# ojacevalec.net
KiCad netlist of a schematic drawn in EAGLE
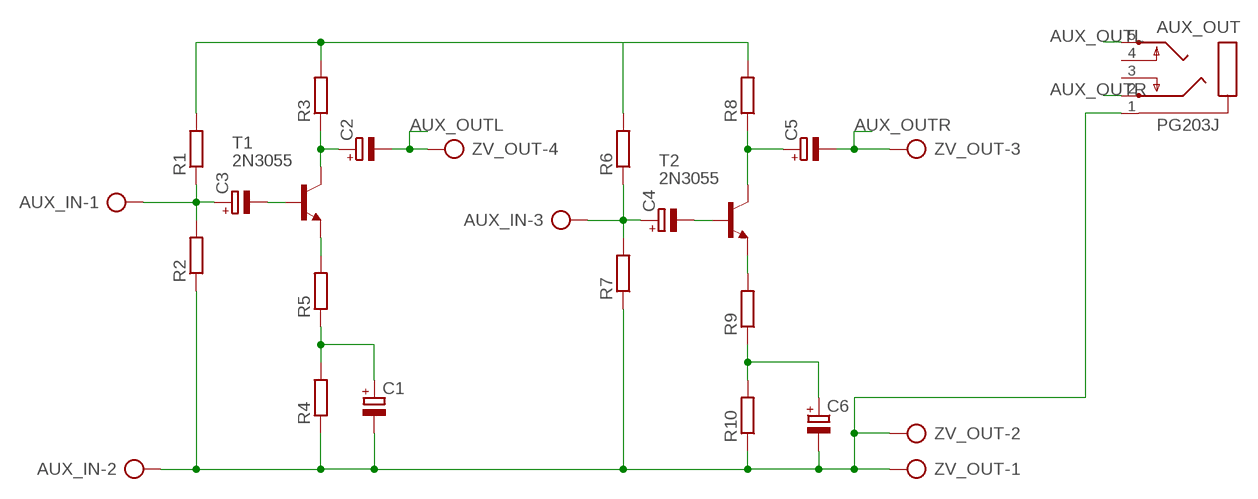
[diagram p0: schematic, sheet 1]

(export (version "E")
  (design (tool "Eeschema 10.0.6"))
  (components
    (comp (ref "AUX_IN")
      (value "AK300/3")
      (footprint "eagle-import:AK300_3")
      (libsource (lib "eagle-import") (part "AK300/3"))
    )
    (comp (ref "AUX_OUT")
      (value "PG203J")
      (footprint "eagle-import:PG203J")
      (libsource (lib "eagle-import") (part "PG203J"))
    )
    (comp (ref "C1")
      (value "CPOL-EUTT5D10")
      (footprint "eagle-import:TT5D10")
      (libsource (lib "eagle-import") (part "CPOL-EUTT5D10"))
    )
    (comp (ref "C2")
      (value "CPOL-EUTT5D10")
      (footprint "eagle-import:TT5D10")
      (libsource (lib "eagle-import") (part "CPOL-EUTT5D10"))
    )
    (comp (ref "C3")
      (value "CPOL-EUTT5D10")
      (footprint "eagle-import:TT5D10")
      (libsource (lib "eagle-import") (part "CPOL-EUTT5D10"))
    )
    (comp (ref "C4")
      (value "CPOL-EUTT5D10")
      (footprint "eagle-import:TT5D10")
      (libsource (lib "eagle-import") (part "CPOL-EUTT5D10"))
    )
    (comp (ref "C5")
      (value "CPOL-EUTT5D10")
      (footprint "eagle-import:TT5D10")
      (libsource (lib "eagle-import") (part "CPOL-EUTT5D10"))
    )
    (comp (ref "C6")
      (value "CPOL-EUTT5D10")
      (footprint "eagle-import:TT5D10")
      (libsource (lib "eagle-import") (part "CPOL-EUTT5D10"))
    )
    (comp (ref "R1")
      (value "R-EU_0309/12")
      (footprint "eagle-import:0309_12")
      (libsource (lib "eagle-import") (part "R-EU_0309/12"))
    )
    (comp (ref "R2")
      (value "R-EU_0309/12")
      (footprint "eagle-import:0309_12")
      (libsource (lib "eagle-import") (part "R-EU_0309/12"))
    )
    (comp (ref "R3")
      (value "R-EU_0309/12")
      (footprint "eagle-import:0309_12")
      (libsource (lib "eagle-import") (part "R-EU_0309/12"))
    )
    (comp (ref "R4")
      (value "R-EU_0309/12")
      (footprint "eagle-import:0309_12")
      (libsource (lib "eagle-import") (part "R-EU_0309/12"))
    )
    (comp (ref "R5")
      (value "R-EU_0309/12")
      (footprint "eagle-import:0309_12")
      (libsource (lib "eagle-import") (part "R-EU_0309/12"))
    )
    (comp (ref "R6")
      (value "R-EU_0309/12")
      (footprint "eagle-import:0309_12")
      (libsource (lib "eagle-import") (part "R-EU_0309/12"))
    )
    (comp (ref "R7")
      (value "R-EU_0309/12")
      (footprint "eagle-import:0309_12")
      (libsource (lib "eagle-import") (part "R-EU_0309/12"))
    )
    (comp (ref "R8")
      (value "R-EU_0309/12")
      (footprint "eagle-import:0309_12")
      (libsource (lib "eagle-import") (part "R-EU_0309/12"))
    )
    (comp (ref "R9")
      (value "R-EU_0309/12")
      (footprint "eagle-import:0309_12")
      (libsource (lib "eagle-import") (part "R-EU_0309/12"))
    )
    (comp (ref "R10")
      (value "R-EU_0309/12")
      (footprint "eagle-import:0309_12")
      (libsource (lib "eagle-import") (part "R-EU_0309/12"))
    )
    (comp (ref "T1")
      (value "2N3055")
      (footprint "eagle-import:TO3")
      (libsource (lib "eagle-import") (part "2N3055"))
    )
    (comp (ref "T2")
      (value "2N3055")
      (footprint "eagle-import:TO3")
      (libsource (lib "eagle-import") (part "2N3055"))
    )
    (comp (ref "ZV_OUT")
      (value "AK300/4")
      (footprint "eagle-import:AK300_4")
      (libsource (lib "eagle-import") (part "AK300/4"))
    )
  )
  (nets
    (net (code "1") (name "/AUX_OUTL") (class "Default")
      (node (ref "AUX_OUT") (pin "5") (pinfunction "5_5") (pintype "passive"))
      (node (ref "C2") (pin "-") (pinfunction "-_-") (pintype "passive"))
      (node (ref "ZV_OUT") (pin "4") (pinfunction "KL_4") (pintype "passive"))
    )
    (net (code "2") (name "/AUX_OUTR") (class "Default")
      (node (ref "AUX_OUT") (pin "2") (pinfunction "2_2") (pintype "passive"))
      (node (ref "C5") (pin "-") (pinfunction "-_-") (pintype "passive"))
      (node (ref "ZV_OUT") (pin "3") (pinfunction "KL_3") (pintype "passive"))
    )
    (net (code "3") (name "Net-(AUX_INA-KL)") (class "Default")
      (node (ref "AUX_IN") (pin "1") (pinfunction "KL_1") (pintype "passive"))
      (node (ref "C3") (pin "+") (pinfunction "+_+") (pintype "passive"))
      (node (ref "R1") (pin "1") (pinfunction "1_1") (pintype "passive"))
      (node (ref "R2") (pin "2") (pinfunction "2_2") (pintype "passive"))
    )
    (net (code "4") (name "Net-(AUX_INB-KL)") (class "Default")
      (node (ref "AUX_IN") (pin "2") (pinfunction "KL_2") (pintype "passive"))
      (node (ref "AUX_OUT") (pin "1") (pinfunction "1_1") (pintype "passive"))
      (node (ref "C1") (pin "-") (pinfunction "-_-") (pintype "passive"))
      (node (ref "C6") (pin "-") (pinfunction "-_-") (pintype "passive"))
      (node (ref "R10") (pin "1") (pinfunction "1_1") (pintype "passive"))
      (node (ref "R2") (pin "1") (pinfunction "1_1") (pintype "passive"))
      (node (ref "R4") (pin "1") (pinfunction "1_1") (pintype "passive"))
      (node (ref "R7") (pin "1") (pinfunction "1_1") (pintype "passive"))
      (node (ref "ZV_OUT") (pin "1") (pinfunction "KL_1") (pintype "passive"))
      (node (ref "ZV_OUT") (pin "2") (pinfunction "KL_2") (pintype "passive"))
    )
    (net (code "5") (name "Net-(AUX_INC-KL)") (class "Default")
      (node (ref "AUX_IN") (pin "3") (pinfunction "KL_3") (pintype "passive"))
      (node (ref "C4") (pin "+") (pinfunction "+_+") (pintype "passive"))
      (node (ref "R6") (pin "1") (pinfunction "1_1") (pintype "passive"))
      (node (ref "R7") (pin "2") (pinfunction "2_2") (pintype "passive"))
    )
    (net (code "6") (name "Net-(C1-Pad+)") (class "Default")
      (node (ref "C1") (pin "+") (pinfunction "+_+") (pintype "passive"))
      (node (ref "R4") (pin "2") (pinfunction "2_2") (pintype "passive"))
      (node (ref "R5") (pin "1") (pinfunction "1_1") (pintype "passive"))
    )
    (net (code "7") (name "Net-(C2-Pad+)") (class "Default")
      (node (ref "C2") (pin "+") (pinfunction "+_+") (pintype "passive"))
      (node (ref "R3") (pin "1") (pinfunction "1_1") (pintype "passive"))
      (node (ref "T1") (pin "C") (pinfunction "C_C") (pintype "passive"))
      (node (ref "T1") (pin "C/") (pinfunction "C_C/") (pintype "passive"))
    )
    (net (code "8") (name "Net-(C3-Pad-)") (class "Default")
      (node (ref "C3") (pin "-") (pinfunction "-_-") (pintype "passive"))
      (node (ref "T1") (pin "B") (pinfunction "B_B") (pintype "passive"))
    )
    (net (code "9") (name "Net-(C4-Pad-)") (class "Default")
      (node (ref "C4") (pin "-") (pinfunction "-_-") (pintype "passive"))
      (node (ref "T2") (pin "B") (pinfunction "B_B") (pintype "passive"))
    )
    (net (code "10") (name "Net-(C5-Pad+)") (class "Default")
      (node (ref "C5") (pin "+") (pinfunction "+_+") (pintype "passive"))
      (node (ref "R8") (pin "1") (pinfunction "1_1") (pintype "passive"))
      (node (ref "T2") (pin "C") (pinfunction "C_C") (pintype "passive"))
      (node (ref "T2") (pin "C/") (pinfunction "C_C/") (pintype "passive"))
    )
    (net (code "11") (name "Net-(C6-Pad+)") (class "Default")
      (node (ref "C6") (pin "+") (pinfunction "+_+") (pintype "passive"))
      (node (ref "R10") (pin "2") (pinfunction "2_2") (pintype "passive"))
      (node (ref "R9") (pin "1") (pinfunction "1_1") (pintype "passive"))
    )
    (net (code "12") (name "Net-(R1-Pad2)") (class "Default")
      (node (ref "R1") (pin "2") (pinfunction "2_2") (pintype "passive"))
      (node (ref "R3") (pin "2") (pinfunction "2_2") (pintype "passive"))
      (node (ref "R6") (pin "2") (pinfunction "2_2") (pintype "passive"))
      (node (ref "R8") (pin "2") (pinfunction "2_2") (pintype "passive"))
    )
    (net (code "13") (name "Net-(R5-Pad2)") (class "Default")
      (node (ref "R5") (pin "2") (pinfunction "2_2") (pintype "passive"))
      (node (ref "T1") (pin "E") (pinfunction "E_E") (pintype "passive"))
    )
    (net (code "14") (name "Net-(R9-Pad2)") (class "Default")
      (node (ref "R9") (pin "2") (pinfunction "2_2") (pintype "passive"))
      (node (ref "T2") (pin "E") (pinfunction "E_E") (pintype "passive"))
    )
    (net (code "15") (name "unconnected-(AUX_OUT-Pad3)") (class "Default")
      (node (ref "AUX_OUT") (pin "3") (pinfunction "3_3") (pintype "passive"))
    )
    (net (code "16") (name "unconnected-(AUX_OUT-Pad4)") (class "Default")
      (node (ref "AUX_OUT") (pin "4") (pinfunction "4_4") (pintype "passive"))
    )
  )
)
